# Propeller_board_rev_1_5.net
KiCad netlist of a schematic drawn in EAGLE
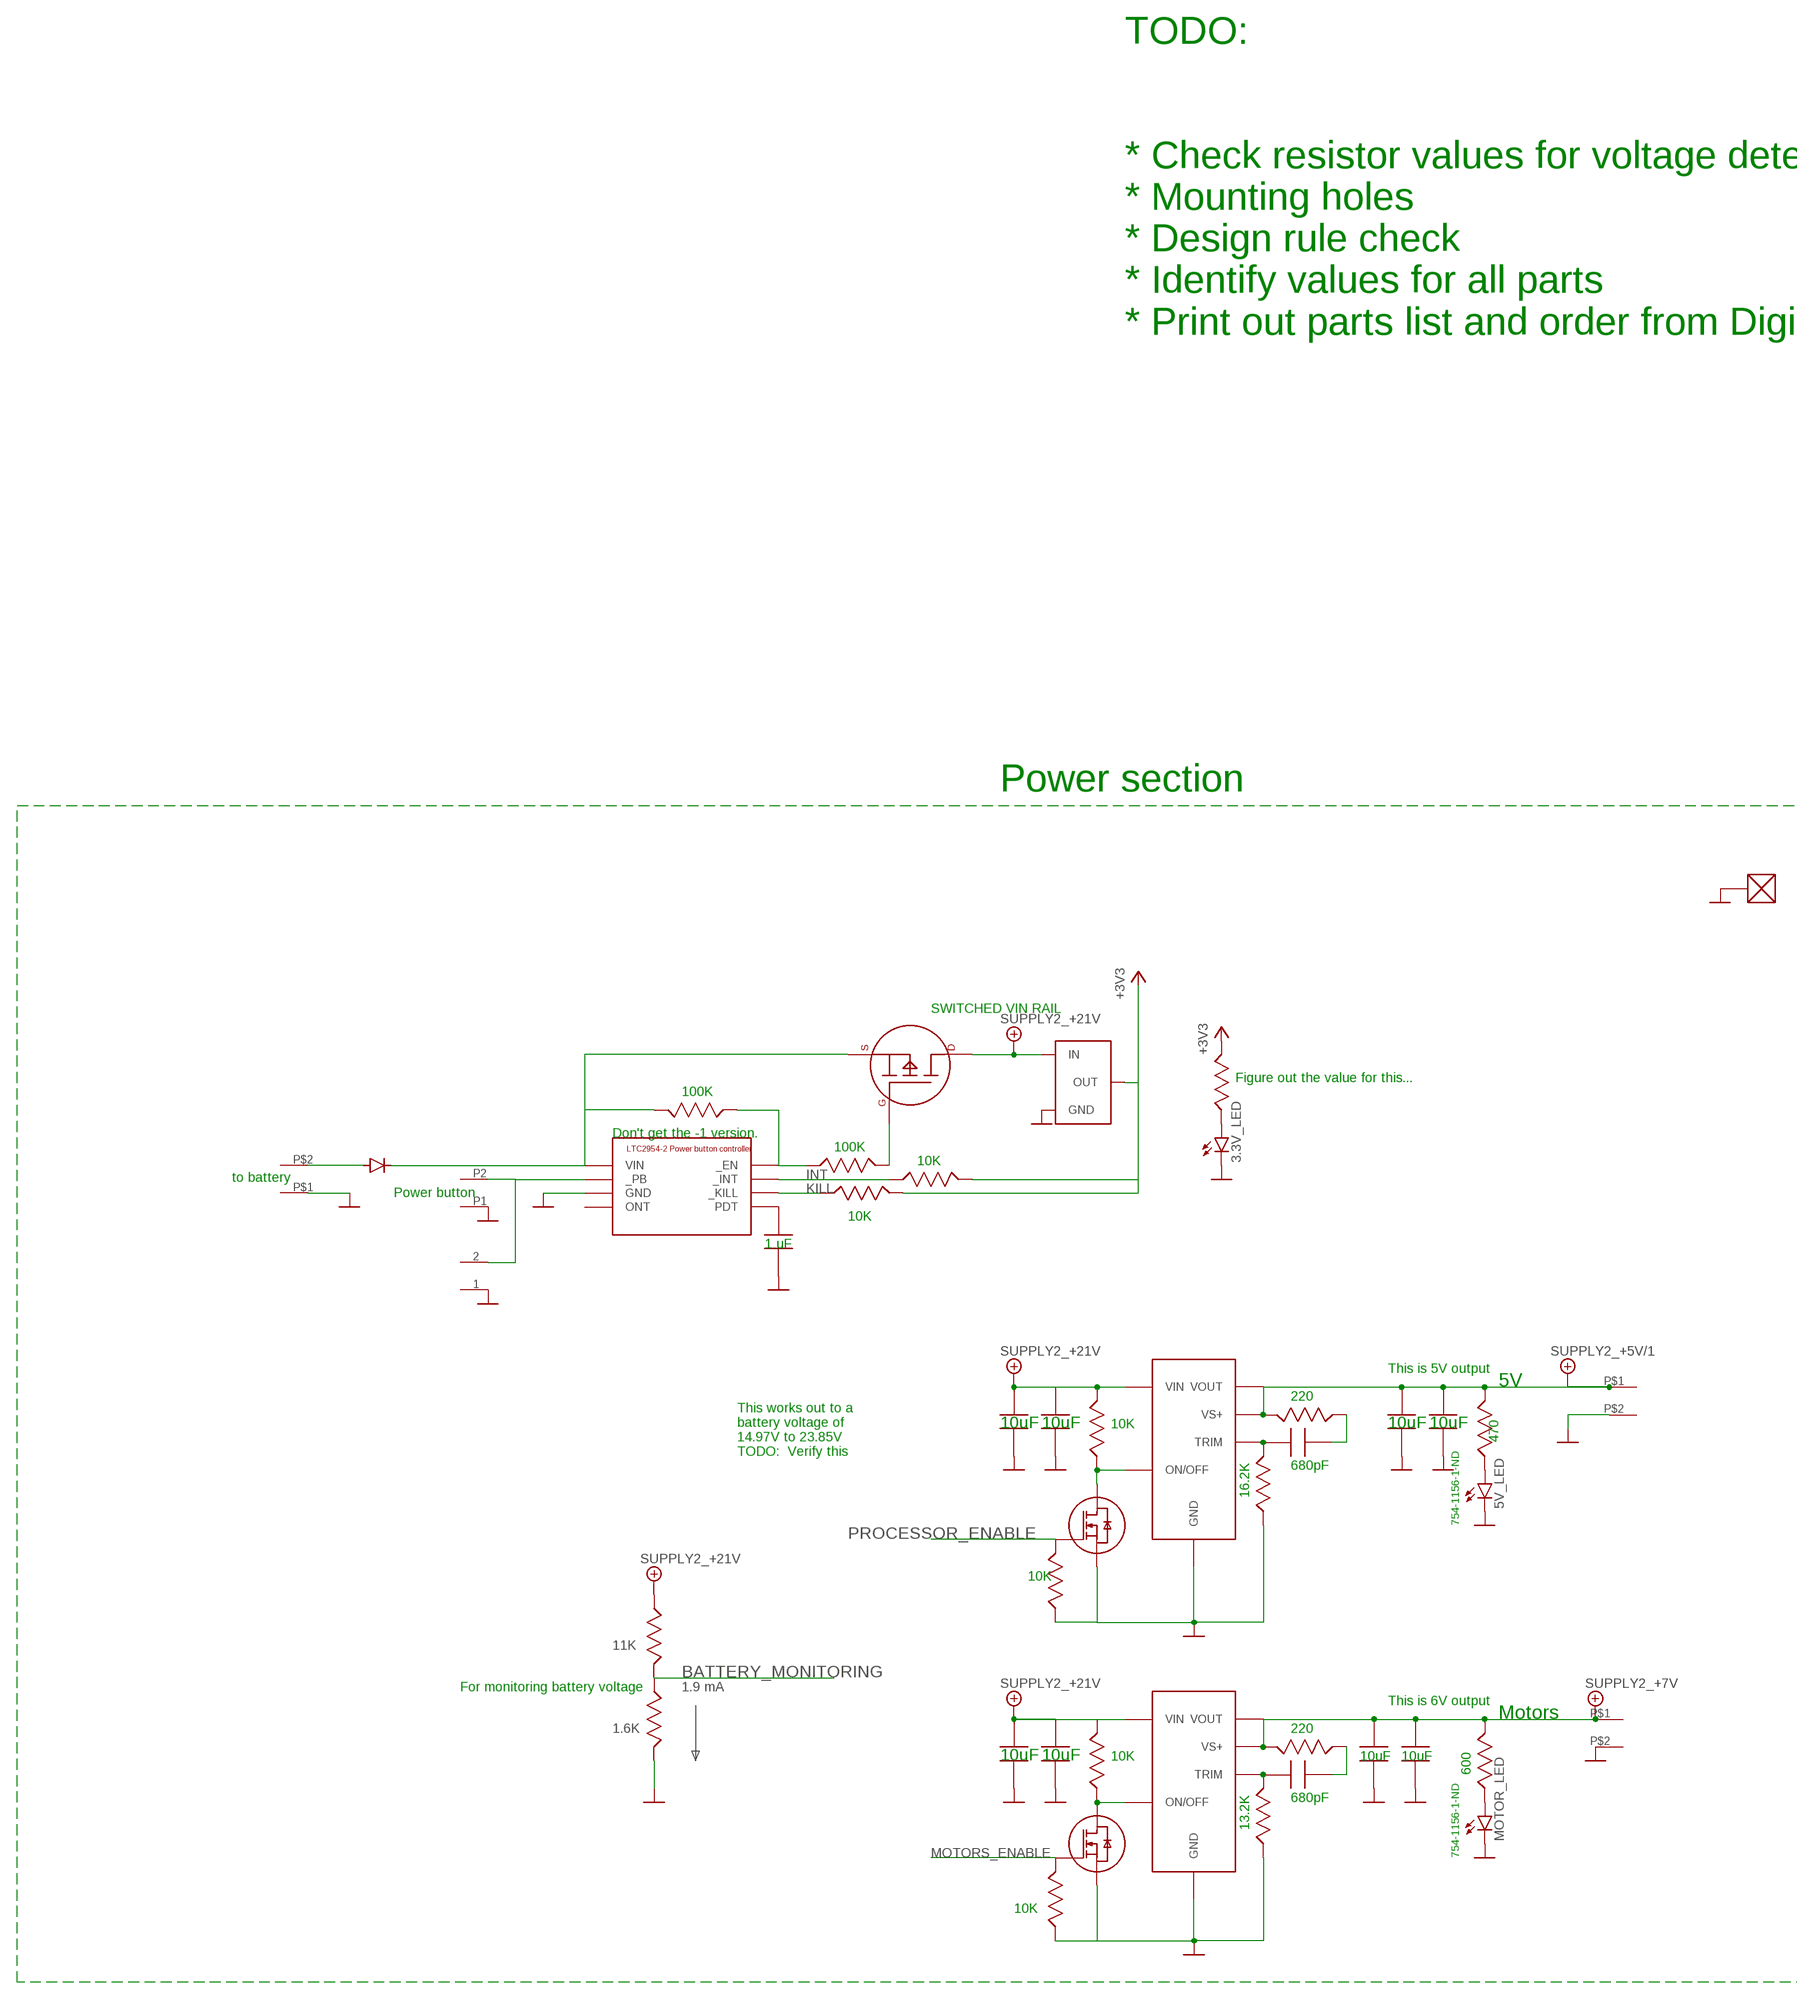
[diagram p0: schematic, sheet 1, part 1 of 2]
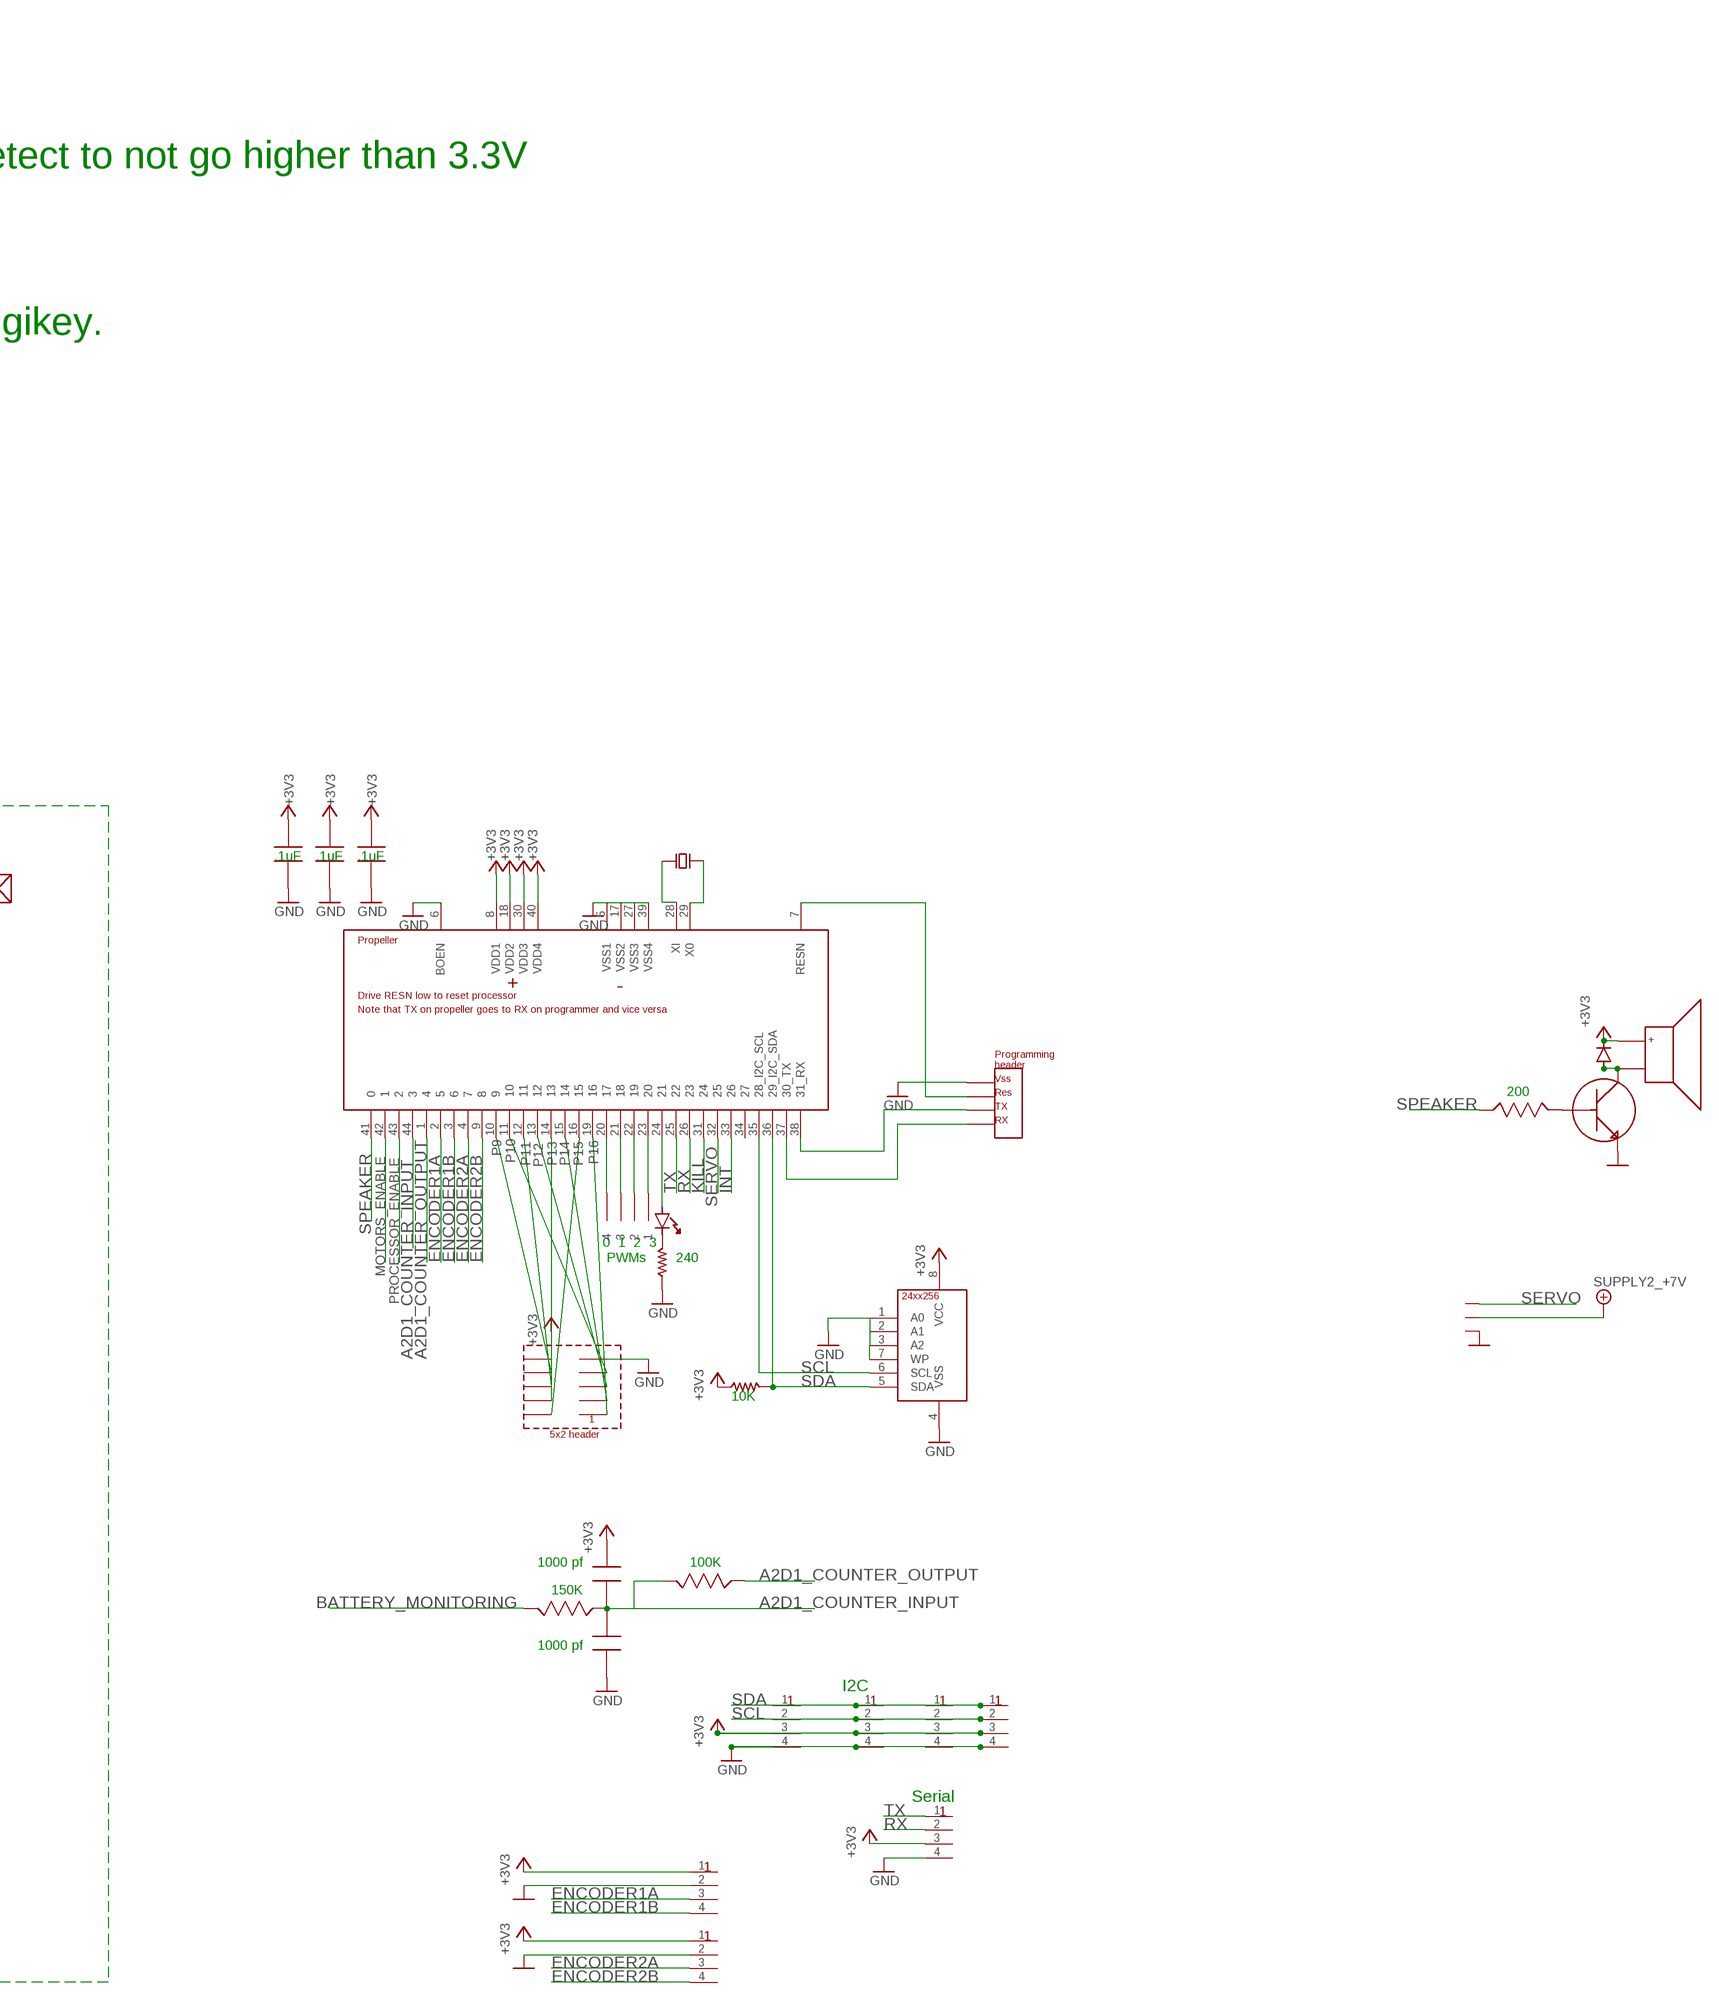
[diagram p1: schematic, sheet 1, part 2 of 2]

(export (version "E")
  (design (tool "Eeschema 10.0.6"))
  (components
    (comp (ref "3.3V_LED")
      (value "LED_LEDSML1206")
      (footprint "eagle-import:LED_SML1206")
      (libsource (lib "eagle-import") (part "LED_LEDSML1206"))
    )
    (comp (ref "3V3_REGULATOR_FOR_PROPELLER")
      (value "VOLTAGE_REGULATOR_3_TERMINALXP_POWER_VR05_SERIES")
      (footprint "eagle-import:VR05_SERIES_VREG")
      (libsource (lib "eagle-import") (part "VOLTAGE_REGULATOR_3_TERMINALXP_POWER_VR05_SERIES"))
    )
    (comp (ref "5V_C_680PF")
      (value "680pf")
      (footprint "eagle-import:JACK_0805")
      (libsource (lib "eagle-import") (part "JACK_CAPACITOR0805"))
    )
    (comp (ref "5V_LED")
      (value "LED_LEDSML1206")
      (footprint "eagle-import:LED_SML1206")
      (libsource (lib "eagle-import") (part "LED_LEDSML1206"))
    )
    (comp (ref "5V_LED_R1")
      (value "470")
      (footprint "eagle-import:JACK_0805")
      (libsource (lib "eagle-import") (part "JACK_RESISTOR0805"))
    )
    (comp (ref "5V_LED_R2")
      (value "470")
      (footprint "eagle-import:JACK_0805")
      (libsource (lib "eagle-import") (part "JACK_RESISTOR0805"))
    )
    (comp (ref "5V_REGULATOR_PULLUP")
      (value "10K")
      (footprint "eagle-import:JACK_0805")
      (libsource (lib "eagle-import") (part "JACK_RESISTOR0805"))
    )
    (comp (ref "5V_R_220")
      (value "220")
      (footprint "eagle-import:JACK_0805")
      (libsource (lib "eagle-import") (part "JACK_RESISTOR0805"))
    )
    (comp (ref "BATTERY_VOLTAGE_DIVIDER_HIGH")
      (value "11K")
      (footprint "eagle-import:JACK_0805")
      (libsource (lib "eagle-import") (part "JACK_RESISTOR0805"))
    )
    (comp (ref "BATTERY_VOLTAGE_DIVIDER_LOW")
      (value "1.6K")
      (footprint "eagle-import:JACK_0805")
      (libsource (lib "eagle-import") (part "JACK_RESISTOR0805"))
    )
    (comp (ref "MOTOR_C_680PF")
      (value "680pf")
      (footprint "eagle-import:JACK_0805")
      (libsource (lib "eagle-import") (part "JACK_CAPACITOR0805"))
    )
    (comp (ref "MOTOR_ENABLE_MOSFET")
      (value "JACK_MOSFET_N_CHANNELBSS138LCT-ND")
      (footprint "eagle-import:JACK_SOT23")
      (libsource (lib "eagle-import") (part "JACK_MOSFET_N_CHANNELBSS138LCT-ND"))
    )
    (comp (ref "MOTOR_ENABLE_MOSFET1")
      (value "JACK_MOSFET_N_CHANNELBSS138LCT-ND")
      (footprint "eagle-import:JACK_SOT23")
      (libsource (lib "eagle-import") (part "JACK_MOSFET_N_CHANNELBSS138LCT-ND"))
    )
    (comp (ref "MOTOR_LED")
      (value "LED_LEDSML1206")
      (footprint "eagle-import:LED_SML1206")
      (libsource (lib "eagle-import") (part "LED_LEDSML1206"))
    )
    (comp (ref "MOTOR_LED_R")
      (value "600")
      (footprint "eagle-import:JACK_0805")
      (libsource (lib "eagle-import") (part "JACK_RESISTOR0805"))
    )
    (comp (ref "MOTOR_MOSFET_PULLDOWN")
      (value "10K")
      (footprint "eagle-import:JACK_0805")
      (libsource (lib "eagle-import") (part "JACK_RESISTOR0805"))
    )
    (comp (ref "MOTOR_PULLUP")
      (value "10K")
      (footprint "eagle-import:JACK_0805")
      (libsource (lib "eagle-import") (part "JACK_RESISTOR0805"))
    )
    (comp (ref "MOTOR_PULLUP2")
      (value "10K")
      (footprint "eagle-import:JACK_0805")
      (libsource (lib "eagle-import") (part "JACK_RESISTOR0805"))
    )
    (comp (ref "MOTOR_R_220")
      (value "220")
      (footprint "eagle-import:JACK_0805")
      (libsource (lib "eagle-import") (part "JACK_RESISTOR0805"))
    )
    (comp (ref "MOTOR_TRIM")
      (value "13.2K")
      (footprint "eagle-import:JACK_0805")
      (libsource (lib "eagle-import") (part "JACK_RESISTOR0805"))
    )
    (comp (ref "R1")
      (value "240")
      (footprint "eagle-import:805_SMD")
      (libsource (lib "eagle-import") (part "jack_custom_RESISTOR0805"))
    )
    (comp (ref "R25")
      (value "10k")
      (footprint "eagle-import:805_SMD")
      (libsource (lib "eagle-import") (part "jack_custom_RESISTOR0805"))
    )
    (comp (ref "RTRIM_5V")
      (value "16.2K")
      (footprint "eagle-import:JACK_0805")
      (libsource (lib "eagle-import") (part "JACK_RESISTOR0805"))
    )
    (comp (ref "U$1")
      (value "CONNECTOR_2_PINJST_PH_SERIES")
      (footprint "eagle-import:JST_2_PIN_PH_SERIES")
      (libsource (lib "eagle-import") (part "CONNECTOR_2_PINJST_PH_SERIES"))
    )
    (comp (ref "U$2")
      (value "JACK_SCREW_TERMINAL_2_CONDUCTORAMP-282837-2")
      (footprint "eagle-import:JACK_AMP-282837-2")
      (libsource (lib "eagle-import") (part "JACK_SCREW_TERMINAL_2_CONDUCTORAMP-282837-2"))
    )
    (comp (ref "U$3")
      (value "POWER_CONTROLLER_LTC2954-2TSOT-23-8")
      (footprint "eagle-import:TSOT-23-8")
      (libsource (lib "eagle-import") (part "POWER_CONTROLLER_LTC2954-2TSOT-23-8"))
    )
    (comp (ref "U$4")
      (value "JACK_DC_TO_DC_VARIABLE_555-1172-1-ND")
      (footprint "eagle-import:JACK_DC2DC_555-1172-1-ND")
      (libsource (lib "eagle-import") (part "JACK_DC_TO_DC_VARIABLE_555-1172-1-ND"))
    )
    (comp (ref "U$5")
      (value "1uf")
      (footprint "eagle-import:0805")
      (libsource (lib "eagle-import") (part "CAPACITOR0805"))
    )
    (comp (ref "U$6")
      (value "JACK_SCREW_TERMINAL_2_CONDUCTORAMP-282837-2")
      (footprint "eagle-import:JACK_AMP-282837-2")
      (libsource (lib "eagle-import") (part "JACK_SCREW_TERMINAL_2_CONDUCTORAMP-282837-2"))
    )
    (comp (ref "U$7")
      (value "100K")
      (footprint "eagle-import:0805")
      (libsource (lib "eagle-import") (part "RESISTOR0805"))
    )
    (comp (ref "U$9")
      (value "100K")
      (footprint "eagle-import:0805")
      (libsource (lib "eagle-import") (part "RESISTOR0805"))
    )
    (comp (ref "U$10")
      (value "10K")
      (footprint "eagle-import:0805")
      (libsource (lib "eagle-import") (part "RESISTOR0805"))
    )
    (comp (ref "U$11")
      (value "1000pF or 1nF")
      (footprint "eagle-import:0805")
      (libsource (lib "eagle-import") (part "CAPACITOR0805"))
    )
    (comp (ref "U$12")
      (value "MOSFET_P_CHANNELSI4431CDY")
      (footprint "eagle-import:SO8")
      (libsource (lib "eagle-import") (part "MOSFET_P_CHANNELSI4431CDY"))
    )
    (comp (ref "U$13")
      (value "JACK_SCREW_TERMINAL_2_CONDUCTORAMP-282837-2")
      (footprint "eagle-import:JACK_AMP-282837-2")
      (libsource (lib "eagle-import") (part "JACK_SCREW_TERMINAL_2_CONDUCTORAMP-282837-2"))
    )
    (comp (ref "U$14")
      (value ".1uf")
      (footprint "eagle-import:0805")
      (libsource (lib "eagle-import") (part "CAPACITOR0805"))
    )
    (comp (ref "U$15")
      (value "CRYSTAL8X4.5_PACKAGE")
      (footprint "eagle-import:CRYSTAL_NX8045GB-5MHZ-STD-CSF-3")
      (libsource (lib "eagle-import") (part "CRYSTAL8X4.5_PACKAGE"))
    )
    (comp (ref "U$16")
      (value ".1uf")
      (footprint "eagle-import:0805")
      (libsource (lib "eagle-import") (part "CAPACITOR0805"))
    )
    (comp (ref "U$17")
      (value "JACK_DC_TO_DC_VARIABLE_555-1172-1-ND")
      (footprint "eagle-import:JACK_DC2DC_555-1172-1-ND")
      (libsource (lib "eagle-import") (part "JACK_DC_TO_DC_VARIABLE_555-1172-1-ND"))
    )
    (comp (ref "U$18")
      (value ".1uf")
      (footprint "eagle-import:0805")
      (libsource (lib "eagle-import") (part "CAPACITOR0805"))
    )
    (comp (ref "U$19")
      (value "TEST_POINT")
      (footprint "eagle-import:KEYSTONE_ELECTRONICS_5118_TEST_POINT")
      (libsource (lib "eagle-import") (part "TEST_POINT"))
    )
    (comp (ref "U$20")
      (value "LED0805")
      (footprint "eagle-import:0805")
      (libsource (lib "eagle-import") (part "LED0805"))
    )
    (comp (ref "U$21")
      (value "HEADER_4_PIN_.1\"")
      (footprint "eagle-import:FOUR_.1__HOLES")
      (libsource (lib "eagle-import") (part "HEADER_4_PIN_.1{dblquote}"))
    )
    (comp (ref "U$22")
      (value "HEADER_5X2")
      (footprint "eagle-import:HEADER_5X2_.1__SPACING")
      (libsource (lib "eagle-import") (part "HEADER_5X2"))
    )
    (comp (ref "U$23")
      (value "CONNECTOR_4_PINJST_PH_SERIES")
      (footprint "eagle-import:JST_4_PIN_PH_SERIES")
      (libsource (lib "eagle-import") (part "CONNECTOR_4_PINJST_PH_SERIES"))
    )
    (comp (ref "U$24")
      (value "CONNECTOR_4_PINJST_PH_SERIES")
      (footprint "eagle-import:JST_4_PIN_PH_SERIES")
      (libsource (lib "eagle-import") (part "CONNECTOR_4_PINJST_PH_SERIES"))
    )
    (comp (ref "U$25")
      (value "CONNECTOR_4_PINJST_PH_SERIES")
      (footprint "eagle-import:JST_4_PIN_PH_SERIES")
      (libsource (lib "eagle-import") (part "CONNECTOR_4_PINJST_PH_SERIES"))
    )
    (comp (ref "U$26")
      (value "CONNECTOR_2_PINJST_.1\"")
      (footprint "eagle-import:JST_2_PIN_.1_")
      (libsource (lib "eagle-import") (part "CONNECTOR_2_PINJST_.1{dblquote}"))
    )
    (comp (ref "U$27")
      (value "10K")
      (footprint "eagle-import:0805")
      (libsource (lib "eagle-import") (part "RESISTOR0805"))
    )
    (comp (ref "U$28")
      (value "10uF")
      (footprint "eagle-import:1210")
      (libsource (lib "eagle-import") (part "CAPACITOR"))
    )
    (comp (ref "U$29")
      (value "10uF")
      (footprint "eagle-import:1210")
      (libsource (lib "eagle-import") (part "CAPACITOR"))
    )
    (comp (ref "U$30")
      (value "10uf")
      (footprint "eagle-import:1210")
      (libsource (lib "eagle-import") (part "CAPACITOR"))
    )
    (comp (ref "U$31")
      (value "10uf")
      (footprint "eagle-import:1210")
      (libsource (lib "eagle-import") (part "CAPACITOR"))
    )
    (comp (ref "U$32")
      (value "10uf")
      (footprint "eagle-import:1210")
      (libsource (lib "eagle-import") (part "CAPACITOR"))
    )
    (comp (ref "U$33")
      (value "10uf")
      (footprint "eagle-import:1210")
      (libsource (lib "eagle-import") (part "CAPACITOR"))
    )
    (comp (ref "U$34")
      (value "SPEAKERGT-0950RP3")
      (footprint "eagle-import:AUDIO_TRANSDUCER_GT-0950RP3")
      (libsource (lib "eagle-import") (part "SPEAKERGT-0950RP3"))
    )
    (comp (ref "U$35")
      (value "DIODESOD523F")
      (footprint "eagle-import:SOD523F")
      (libsource (lib "eagle-import") (part "DIODESOD523F"))
    )
    (comp (ref "U$36")
      (value "TRANSISTOR_NPNMMBT3904")
      (footprint "eagle-import:SOT23")
      (libsource (lib "eagle-import") (part "TRANSISTOR_NPNMMBT3904"))
    )
    (comp (ref "U$37")
      (value "200")
      (footprint "eagle-import:0805")
      (libsource (lib "eagle-import") (part "RESISTOR0805"))
    )
    (comp (ref "U$38")
      (value "CONNECTOR_3_PIN.1\"SPACING")
      (footprint "eagle-import:THREE_.1__HOLES")
      (libsource (lib "eagle-import") (part "CONNECTOR_3_PIN.1{dblquote}SPACING"))
    )
    (comp (ref "U$39")
      (value "DIODEPOWER_DI15")
      (footprint "eagle-import:POWER_DI15")
      (libsource (lib "eagle-import") (part "DIODEPOWER_DI15"))
    )
    (comp (ref "U$40")
      (value "10uf")
      (footprint "eagle-import:1210")
      (libsource (lib "eagle-import") (part "CAPACITOR"))
    )
    (comp (ref "U$41")
      (value "10uf")
      (footprint "eagle-import:1210")
      (libsource (lib "eagle-import") (part "CAPACITOR"))
    )
    (comp (ref "U$42")
      (value "1000pf or 1 nF")
      (footprint "eagle-import:0805")
      (libsource (lib "eagle-import") (part "CAPACITOR0805"))
    )
    (comp (ref "U$43")
      (value "150K")
      (footprint "eagle-import:0805")
      (libsource (lib "eagle-import") (part "RESISTOR0805"))
    )
    (comp (ref "U$44")
      (value "100K")
      (footprint "eagle-import:0805")
      (libsource (lib "eagle-import") (part "RESISTOR0805"))
    )
    (comp (ref "U$45")
      (value "CONNECTOR_4_PINJST_PH_SERIES")
      (footprint "eagle-import:JST_4_PIN_PH_SERIES")
      (libsource (lib "eagle-import") (part "CONNECTOR_4_PINJST_PH_SERIES"))
    )
    (comp (ref "U$46")
      (value "CONNECTOR_4_PINJST_PH_SERIES")
      (footprint "eagle-import:JST_4_PIN_PH_SERIES")
      (libsource (lib "eagle-import") (part "CONNECTOR_4_PINJST_PH_SERIES"))
    )
    (comp (ref "U$47")
      (value "CONNECTOR_4_PINJST_PH_SERIES")
      (footprint "eagle-import:JST_4_PIN_PH_SERIES")
      (libsource (lib "eagle-import") (part "CONNECTOR_4_PINJST_PH_SERIES"))
    )
    (comp (ref "U$48")
      (value "PROPELLER_PROGRAMMING_HEADERHOLES")
      (footprint "eagle-import:FOUR_.1_HOLES")
      (libsource (lib "eagle-import") (part "PROPELLER_PROGRAMMING_HEADERHOLES"))
    )
    (comp (ref "U$49")
      (value "CONNECTOR_4_PINJST_PH_SERIES")
      (footprint "eagle-import:JST_4_PIN_PH_SERIES")
      (libsource (lib "eagle-import") (part "CONNECTOR_4_PINJST_PH_SERIES"))
    )
    (comp (ref "U1")
      (value "PARALLAX_PROPELLER")
      (footprint "eagle-import:44LQFP")
      (libsource (lib "eagle-import") (part "PARALLAX_PROPELLER"))
    )
    (comp (ref "U2")
      (value "EEPROM_24XX256")
      (footprint "eagle-import:8_MSOP")
      (libsource (lib "eagle-import") (part "EEPROM_24XX256"))
    )
  )
  (nets
    (net (code "1") (name "+3V3") (class "Default")
      (node (ref "3V3_REGULATOR_FOR_PROPELLER") (pin "VOUT") (pinfunction "OUT_VOUT") (pintype "bidirectional"))
      (node (ref "5V_LED_R2") (pin "P$3") (pinfunction "P$3_P$3") (pintype "bidirectional"))
      (node (ref "R25") (pin "P$1") (pinfunction "P$1_P$1") (pintype "bidirectional"))
      (node (ref "U$10") (pin "C2") (pinfunction "P$3_C2") (pintype "bidirectional"))
      (node (ref "U$11") (pin "C2") (pinfunction "2-_C2") (pintype "bidirectional"))
      (node (ref "U$14") (pin "C2") (pinfunction "2-_C2") (pintype "bidirectional"))
      (node (ref "U$16") (pin "C2") (pinfunction "2-_C2") (pintype "bidirectional"))
      (node (ref "U$18") (pin "C2") (pinfunction "2-_C2") (pintype "bidirectional"))
      (node (ref "U$22") (pin "P10") (pinfunction "10_P10") (pintype "bidirectional"))
      (node (ref "U$23") (pin "3") (pinfunction "P$3_3") (pintype "bidirectional"))
      (node (ref "U$24") (pin "3") (pinfunction "P$3_3") (pintype "bidirectional"))
      (node (ref "U$25") (pin "3") (pinfunction "P$3_3") (pintype "bidirectional"))
      (node (ref "U$27") (pin "C2") (pinfunction "P$3_C2") (pintype "bidirectional"))
      (node (ref "U$34") (pin "+") (pinfunction "+_+") (pintype "bidirectional"))
      (node (ref "U$35") (pin "C") (pinfunction "C_C") (pintype "bidirectional"))
      (node (ref "U$45") (pin "3") (pinfunction "P$3_3") (pintype "bidirectional"))
      (node (ref "U$46") (pin "1") (pinfunction "P$1_1") (pintype "bidirectional"))
      (node (ref "U$47") (pin "3") (pinfunction "P$3_3") (pintype "bidirectional"))
      (node (ref "U$49") (pin "1") (pinfunction "P$1_1") (pintype "bidirectional"))
      (node (ref "U1") (pin "18") (pinfunction "VDD2_18") (pintype "bidirectional"))
      (node (ref "U1") (pin "30") (pinfunction "VDD3_30") (pintype "bidirectional"))
      (node (ref "U1") (pin "40") (pinfunction "VDD4_40") (pintype "bidirectional"))
      (node (ref "U1") (pin "8") (pinfunction "VDD1_8") (pintype "bidirectional"))
      (node (ref "U2") (pin "8") (pinfunction "VCC_8") (pintype "bidirectional"))
    )
    (net (code "2") (name "/A2D1_COUNTER_INPUT") (class "Default")
      (node (ref "U$11") (pin "A1") (pinfunction "1+_A1") (pintype "bidirectional"))
      (node (ref "U$42") (pin "C2") (pinfunction "2-_C2") (pintype "bidirectional"))
      (node (ref "U$43") (pin "A1") (pinfunction "P$2_A1") (pintype "bidirectional"))
      (node (ref "U$44") (pin "C2") (pinfunction "P$3_C2") (pintype "bidirectional"))
      (node (ref "U1") (pin "44") (pinfunction "3_44") (pintype "bidirectional"))
    )
    (net (code "3") (name "/A2D1_COUNTER_OUTPUT") (class "Default")
      (node (ref "U$44") (pin "A1") (pinfunction "P$2_A1") (pintype "bidirectional"))
      (node (ref "U1") (pin "1") (pinfunction "4_1") (pintype "bidirectional"))
    )
    (net (code "4") (name "/BATTERY_MONITORING") (class "Default")
      (node (ref "BATTERY_VOLTAGE_DIVIDER_HIGH") (pin "P$3") (pinfunction "P$3_P$3") (pintype "bidirectional"))
      (node (ref "BATTERY_VOLTAGE_DIVIDER_LOW") (pin "P$2") (pinfunction "P$2_P$2") (pintype "bidirectional"))
      (node (ref "U$43") (pin "C2") (pinfunction "P$3_C2") (pintype "bidirectional"))
    )
    (net (code "5") (name "/ENCODER1A") (class "Default")
      (node (ref "U$46") (pin "3") (pinfunction "P$3_3") (pintype "bidirectional"))
      (node (ref "U1") (pin "2") (pinfunction "5_2") (pintype "bidirectional"))
    )
    (net (code "6") (name "/ENCODER1B") (class "Default")
      (node (ref "U$46") (pin "4") (pinfunction "P$4_4") (pintype "bidirectional"))
      (node (ref "U1") (pin "3") (pinfunction "6_3") (pintype "bidirectional"))
    )
    (net (code "7") (name "/ENCODER2A") (class "Default")
      (node (ref "U$49") (pin "3") (pinfunction "P$3_3") (pintype "bidirectional"))
      (node (ref "U1") (pin "4") (pinfunction "7_4") (pintype "bidirectional"))
    )
    (net (code "8") (name "/ENCODER2B") (class "Default")
      (node (ref "U$49") (pin "4") (pinfunction "P$4_4") (pintype "bidirectional"))
      (node (ref "U1") (pin "9") (pinfunction "8_9") (pintype "bidirectional"))
    )
    (net (code "9") (name "/INT") (class "Default")
      (node (ref "U$10") (pin "A1") (pinfunction "P$2_A1") (pintype "bidirectional"))
      (node (ref "U$3") (pin "5") (pinfunction "_INT_5") (pintype "bidirectional"))
      (node (ref "U1") (pin "33") (pinfunction "26_33") (pintype "bidirectional"))
    )
    (net (code "10") (name "/KILL") (class "Default")
      (node (ref "U$27") (pin "A1") (pinfunction "P$2_A1") (pintype "bidirectional"))
      (node (ref "U$3") (pin "8") (pinfunction "_KILL_8") (pintype "bidirectional"))
      (node (ref "U1") (pin "31") (pinfunction "24_31") (pintype "bidirectional"))
    )
    (net (code "11") (name "/MOTORS_ENABLE") (class "Default")
      (node (ref "MOTOR_ENABLE_MOSFET") (pin "1") (pinfunction "G_1") (pintype "bidirectional"))
      (node (ref "MOTOR_MOSFET_PULLDOWN") (pin "P$3") (pinfunction "P$3_P$3") (pintype "bidirectional"))
      (node (ref "U1") (pin "42") (pinfunction "1_42") (pintype "bidirectional"))
    )
    (net (code "12") (name "/P9") (class "Default")
      (node (ref "U$22") (pin "P8") (pinfunction "8_P8") (pintype "bidirectional"))
      (node (ref "U1") (pin "10") (pinfunction "9_10") (pintype "bidirectional"))
    )
    (net (code "13") (name "/P10") (class "Default")
      (node (ref "U$22") (pin "P7") (pinfunction "7_P7") (pintype "bidirectional"))
      (node (ref "U1") (pin "11") (pinfunction "10_11") (pintype "bidirectional"))
    )
    (net (code "14") (name "/P11") (class "Default")
      (node (ref "U$22") (pin "P6") (pinfunction "6_P6") (pintype "bidirectional"))
      (node (ref "U1") (pin "12") (pinfunction "11_12") (pintype "bidirectional"))
    )
    (net (code "15") (name "/P12") (class "Default")
      (node (ref "U$22") (pin "P5") (pinfunction "5_P5") (pintype "bidirectional"))
      (node (ref "U1") (pin "13") (pinfunction "12_13") (pintype "bidirectional"))
    )
    (net (code "16") (name "/P13") (class "Default")
      (node (ref "U$22") (pin "P4") (pinfunction "4_P4") (pintype "bidirectional"))
      (node (ref "U1") (pin "14") (pinfunction "13_14") (pintype "bidirectional"))
    )
    (net (code "17") (name "/P14") (class "Default")
      (node (ref "U$22") (pin "P3") (pinfunction "3_P3") (pintype "bidirectional"))
      (node (ref "U1") (pin "15") (pinfunction "14_15") (pintype "bidirectional"))
    )
    (net (code "18") (name "/P15") (class "Default")
      (node (ref "U$22") (pin "P2") (pinfunction "2_P2") (pintype "bidirectional"))
      (node (ref "U1") (pin "16") (pinfunction "15_16") (pintype "bidirectional"))
    )
    (net (code "19") (name "/P16") (class "Default")
      (node (ref "U$22") (pin "P1") (pinfunction "1_P1") (pintype "bidirectional"))
      (node (ref "U1") (pin "19") (pinfunction "16_19") (pintype "bidirectional"))
    )
    (net (code "20") (name "/PROCESSOR_ENABLE") (class "Default")
      (node (ref "MOTOR_ENABLE_MOSFET1") (pin "1") (pinfunction "G_1") (pintype "bidirectional"))
      (node (ref "MOTOR_PULLUP2") (pin "P$3") (pinfunction "P$3_P$3") (pintype "bidirectional"))
      (node (ref "U1") (pin "43") (pinfunction "2_43") (pintype "bidirectional"))
    )
    (net (code "21") (name "/RX") (class "Default")
      (node (ref "U$47") (pin "2") (pinfunction "P$2_2") (pintype "bidirectional"))
      (node (ref "U1") (pin "26") (pinfunction "23_26") (pintype "bidirectional"))
    )
    (net (code "22") (name "/SCL") (class "Default")
      (node (ref "U$23") (pin "2") (pinfunction "P$2_2") (pintype "bidirectional"))
      (node (ref "U$24") (pin "2") (pinfunction "P$2_2") (pintype "bidirectional"))
      (node (ref "U$25") (pin "2") (pinfunction "P$2_2") (pintype "bidirectional"))
      (node (ref "U$45") (pin "2") (pinfunction "P$2_2") (pintype "bidirectional"))
      (node (ref "U1") (pin "35") (pinfunction "28_I2C_SCL_35") (pintype "bidirectional"))
      (node (ref "U2") (pin "6") (pinfunction "SCL_6") (pintype "bidirectional"))
    )
    (net (code "23") (name "/SDA") (class "Default")
      (node (ref "R25") (pin "P$2") (pinfunction "P$2_P$2") (pintype "bidirectional"))
      (node (ref "U$23") (pin "1") (pinfunction "P$1_1") (pintype "bidirectional"))
      (node (ref "U$24") (pin "1") (pinfunction "P$1_1") (pintype "bidirectional"))
      (node (ref "U$25") (pin "1") (pinfunction "P$1_1") (pintype "bidirectional"))
      (node (ref "U$45") (pin "1") (pinfunction "P$1_1") (pintype "bidirectional"))
      (node (ref "U1") (pin "36") (pinfunction "29_I2C_SDA_36") (pintype "bidirectional"))
      (node (ref "U2") (pin "5") (pinfunction "SDA_5") (pintype "bidirectional"))
    )
    (net (code "24") (name "/SERVO") (class "Default")
      (node (ref "U$38") (pin "3") (pinfunction "3_3") (pintype "bidirectional"))
      (node (ref "U1") (pin "32") (pinfunction "25_32") (pintype "bidirectional"))
    )
    (net (code "25") (name "/SPEAKER") (class "Default")
      (node (ref "U$37") (pin "A1") (pinfunction "P$2_A1") (pintype "bidirectional"))
      (node (ref "U1") (pin "41") (pinfunction "0_41") (pintype "bidirectional"))
    )
    (net (code "26") (name "/TX") (class "Default")
      (node (ref "U$47") (pin "1") (pinfunction "P$1_1") (pintype "bidirectional"))
      (node (ref "U1") (pin "25") (pinfunction "22_25") (pintype "bidirectional"))
    )
    (net (code "27") (name "GND") (class "Default")
      (node (ref "3.3V_LED") (pin "C") (pinfunction "C_C") (pintype "passive"))
      (node (ref "3V3_REGULATOR_FOR_PROPELLER") (pin "GND") (pinfunction "GND_GND") (pintype "bidirectional"))
      (node (ref "5V_LED") (pin "C") (pinfunction "C_C") (pintype "passive"))
      (node (ref "BATTERY_VOLTAGE_DIVIDER_LOW") (pin "P$3") (pinfunction "P$3_P$3") (pintype "bidirectional"))
      (node (ref "MOTOR_ENABLE_MOSFET") (pin "2") (pinfunction "S_2") (pintype "bidirectional"))
      (node (ref "MOTOR_ENABLE_MOSFET1") (pin "2") (pinfunction "S_2") (pintype "bidirectional"))
      (node (ref "MOTOR_LED") (pin "C") (pinfunction "C_C") (pintype "passive"))
      (node (ref "MOTOR_MOSFET_PULLDOWN") (pin "P$2") (pinfunction "P$2_P$2") (pintype "bidirectional"))
      (node (ref "MOTOR_PULLUP2") (pin "P$2") (pinfunction "P$2_P$2") (pintype "bidirectional"))
      (node (ref "MOTOR_TRIM") (pin "P$2") (pinfunction "P$2_P$2") (pintype "bidirectional"))
      (node (ref "R1") (pin "P$1") (pinfunction "P$1_P$1") (pintype "bidirectional"))
      (node (ref "RTRIM_5V") (pin "P$2") (pinfunction "P$2_P$2") (pintype "bidirectional"))
      (node (ref "U$1") (pin "P1") (pinfunction "P$1_P1") (pintype "bidirectional"))
      (node (ref "U$13") (pin "P$2") (pinfunction "P$2_P$2") (pintype "bidirectional"))
      (node (ref "U$14") (pin "A1") (pinfunction "1+_A1") (pintype "bidirectional"))
      (node (ref "U$16") (pin "A1") (pinfunction "1+_A1") (pintype "bidirectional"))
      (node (ref "U$17") (pin "GND") (pinfunction "GND_GND") (pintype "bidirectional"))
      (node (ref "U$18") (pin "A1") (pinfunction "1+_A1") (pintype "bidirectional"))
      (node (ref "U$19") (pin "P1") (pinfunction "P$1_P1") (pintype "bidirectional"))
      (node (ref "U$2") (pin "P$2") (pinfunction "P$2_P$2") (pintype "bidirectional"))
      (node (ref "U$22") (pin "P9") (pinfunction "9_P9") (pintype "bidirectional"))
      (node (ref "U$23") (pin "4") (pinfunction "P$4_4") (pintype "bidirectional"))
      (node (ref "U$24") (pin "4") (pinfunction "P$4_4") (pintype "bidirectional"))
      (node (ref "U$25") (pin "4") (pinfunction "P$4_4") (pintype "bidirectional"))
      (node (ref "U$26") (pin "1") (pinfunction "P$1_1") (pintype "bidirectional"))
      (node (ref "U$28") (pin "1") (pinfunction "1+_1") (pintype "bidirectional"))
      (node (ref "U$29") (pin "1") (pinfunction "1+_1") (pintype "bidirectional"))
      (node (ref "U$3") (pin "4") (pinfunction "GND_4") (pintype "bidirectional"))
      (node (ref "U$30") (pin "1") (pinfunction "1+_1") (pintype "bidirectional"))
      (node (ref "U$31") (pin "1") (pinfunction "1+_1") (pintype "bidirectional"))
      (node (ref "U$32") (pin "1") (pinfunction "1+_1") (pintype "bidirectional"))
      (node (ref "U$33") (pin "1") (pinfunction "1+_1") (pintype "bidirectional"))
      (node (ref "U$36") (pin "2") (pinfunction "E_2") (pintype "bidirectional"))
      (node (ref "U$38") (pin "1") (pinfunction "1_1") (pintype "bidirectional"))
      (node (ref "U$4") (pin "GND") (pinfunction "GND_GND") (pintype "bidirectional"))
      (node (ref "U$40") (pin "1") (pinfunction "1+_1") (pintype "bidirectional"))
      (node (ref "U$41") (pin "1") (pinfunction "1+_1") (pintype "bidirectional"))
      (node (ref "U$42") (pin "A1") (pinfunction "1+_A1") (pintype "bidirectional"))
      (node (ref "U$45") (pin "4") (pinfunction "P$4_4") (pintype "bidirectional"))
      (node (ref "U$46") (pin "2") (pinfunction "P$2_2") (pintype "bidirectional"))
      (node (ref "U$47") (pin "4") (pinfunction "P$4_4") (pintype "bidirectional"))
      (node (ref "U$48") (pin "1") (pinfunction "VSS_1") (pintype "bidirectional"))
      (node (ref "U$49") (pin "2") (pinfunction "P$2_2") (pintype "bidirectional"))
      (node (ref "U$5") (pin "A1") (pinfunction "1+_A1") (pintype "bidirectional"))
      (node (ref "U$6") (pin "P$1") (pinfunction "P$1_P$1") (pintype "bidirectional"))
      (node (ref "U1") (pin "17") (pinfunction "VSS2_17") (pintype "bidirectional"))
      (node (ref "U1") (pin "27") (pinfunction "VSS3_27") (pintype "bidirectional"))
      (node (ref "U1") (pin "39") (pinfunction "VSS4_39") (pintype "bidirectional"))
      (node (ref "U1") (pin "5") (pinfunction "VSS1_5") (pintype "bidirectional"))
      (node (ref "U1") (pin "6") (pinfunction "BOEN_6") (pintype "bidirectional"))
      (node (ref "U2") (pin "1") (pinfunction "A0_1") (pintype "bidirectional"))
      (node (ref "U2") (pin "2") (pinfunction "A1_2") (pintype "bidirectional"))
      (node (ref "U2") (pin "3") (pinfunction "A2_3") (pintype "bidirectional"))
      (node (ref "U2") (pin "4") (pinfunction "VSS_4") (pintype "bidirectional"))
      (node (ref "U2") (pin "7") (pinfunction "WP_7") (pintype "bidirectional"))
    )
    (net (code "28") (name "Net-(3.3V_LED-PadA)") (class "Default")
      (node (ref "3.3V_LED") (pin "A") (pinfunction "A_A") (pintype "passive"))
      (node (ref "5V_LED_R2") (pin "P$2") (pinfunction "P$2_P$2") (pintype "bidirectional"))
    )
    (net (code "29") (name "Net-(5V_C_680PF-1)") (class "Default")
      (node (ref "5V_C_680PF") (pin "P$2") (pinfunction "1_P$2") (pintype "bidirectional"))
      (node (ref "5V_R_220") (pin "P$2") (pinfunction "P$2_P$2") (pintype "bidirectional"))
    )
    (net (code "30") (name "Net-(5V_C_680PF-2)") (class "Default")
      (node (ref "5V_C_680PF") (pin "P$3") (pinfunction "2_P$3") (pintype "bidirectional"))
      (node (ref "RTRIM_5V") (pin "P$3") (pinfunction "P$3_P$3") (pintype "bidirectional"))
      (node (ref "U$4") (pin "TRIM") (pinfunction "TRIM_TRIM") (pintype "bidirectional"))
    )
    (net (code "31") (name "Net-(5V_LED-PadA)") (class "Default")
      (node (ref "5V_LED") (pin "A") (pinfunction "A_A") (pintype "passive"))
      (node (ref "5V_LED_R1") (pin "P$2") (pinfunction "P$2_P$2") (pintype "bidirectional"))
    )
    (net (code "32") (name "Net-(MOTOR_C_680PF-1)") (class "Default")
      (node (ref "MOTOR_C_680PF") (pin "P$2") (pinfunction "1_P$2") (pintype "bidirectional"))
      (node (ref "MOTOR_R_220") (pin "P$2") (pinfunction "P$2_P$2") (pintype "bidirectional"))
    )
    (net (code "33") (name "Net-(MOTOR_C_680PF-2)") (class "Default")
      (node (ref "MOTOR_C_680PF") (pin "P$3") (pinfunction "2_P$3") (pintype "bidirectional"))
      (node (ref "MOTOR_TRIM") (pin "P$3") (pinfunction "P$3_P$3") (pintype "bidirectional"))
      (node (ref "U$17") (pin "TRIM") (pinfunction "TRIM_TRIM") (pintype "bidirectional"))
    )
    (net (code "34") (name "Net-(MOTOR_ENABLE_MOSFET-D)") (class "Default")
      (node (ref "MOTOR_ENABLE_MOSFET") (pin "3") (pinfunction "D_3") (pintype "bidirectional"))
      (node (ref "MOTOR_PULLUP") (pin "P$2") (pinfunction "P$2_P$2") (pintype "bidirectional"))
      (node (ref "U$17") (pin "ON/OFF") (pinfunction "ON/OFF_ON/OFF") (pintype "bidirectional"))
    )
    (net (code "35") (name "Net-(MOTOR_ENABLE_MOSFET1-D)") (class "Default")
      (node (ref "5V_REGULATOR_PULLUP") (pin "P$2") (pinfunction "P$2_P$2") (pintype "bidirectional"))
      (node (ref "MOTOR_ENABLE_MOSFET1") (pin "3") (pinfunction "D_3") (pintype "bidirectional"))
      (node (ref "U$4") (pin "ON/OFF") (pinfunction "ON/OFF_ON/OFF") (pintype "bidirectional"))
    )
    (net (code "36") (name "Net-(MOTOR_LED-PadA)") (class "Default")
      (node (ref "MOTOR_LED") (pin "A") (pinfunction "A_A") (pintype "passive"))
      (node (ref "MOTOR_LED_R") (pin "P$2") (pinfunction "P$2_P$2") (pintype "bidirectional"))
    )
    (net (code "37") (name "Net-(U$1-P$2)") (class "Default")
      (node (ref "U$1") (pin "P2") (pinfunction "P$2_P2") (pintype "bidirectional"))
      (node (ref "U$26") (pin "2") (pinfunction "P$2_2") (pintype "bidirectional"))
      (node (ref "U$3") (pin "2") (pinfunction "_PB_2") (pintype "bidirectional"))
    )
    (net (code "38") (name "Net-(U$3-PDT)") (class "Default")
      (node (ref "U$3") (pin "7") (pinfunction "PDT_7") (pintype "bidirectional"))
      (node (ref "U$5") (pin "C2") (pinfunction "2-_C2") (pintype "bidirectional"))
    )
    (net (code "39") (name "Net-(U$3-VIN)") (class "Default")
      (node (ref "U$12") (pin "1") (pinfunction "S_1") (pintype "bidirectional"))
      (node (ref "U$12") (pin "2") (pinfunction "S_2") (pintype "bidirectional"))
      (node (ref "U$12") (pin "3") (pinfunction "S_3") (pintype "bidirectional"))
      (node (ref "U$3") (pin "1") (pinfunction "VIN_1") (pintype "bidirectional"))
      (node (ref "U$39") (pin "3") (pinfunction "C_3") (pintype "bidirectional"))
      (node (ref "U$7") (pin "C2") (pinfunction "P$3_C2") (pintype "bidirectional"))
    )
    (net (code "40") (name "Net-(U$3-_EN)") (class "Default")
      (node (ref "U$3") (pin "6") (pinfunction "_EN_6") (pintype "bidirectional"))
      (node (ref "U$7") (pin "A1") (pinfunction "P$2_A1") (pintype "bidirectional"))
      (node (ref "U$9") (pin "A1") (pinfunction "P$2_A1") (pintype "bidirectional"))
    )
    (net (code "41") (name "Net-(U$12-G)") (class "Default")
      (node (ref "U$12") (pin "4") (pinfunction "G_4") (pintype "bidirectional"))
      (node (ref "U$9") (pin "C2") (pinfunction "P$3_C2") (pintype "bidirectional"))
    )
    (net (code "42") (name "Net-(U$15-P$3)") (class "Default")
      (node (ref "U$15") (pin "1") (pinfunction "P$3_1") (pintype "bidirectional"))
      (node (ref "U1") (pin "28") (pinfunction "XI_28") (pintype "bidirectional"))
    )
    (net (code "43") (name "Net-(U$15-P$4)") (class "Default")
      (node (ref "U$15") (pin "2") (pinfunction "P$4_2") (pintype "bidirectional"))
      (node (ref "U1") (pin "29") (pinfunction "X0_29") (pintype "bidirectional"))
    )
    (net (code "44") (name "Net-(U$20-A)") (class "Default")
      (node (ref "U$20") (pin "A1") (pinfunction "A_A1") (pintype "bidirectional"))
      (node (ref "U1") (pin "24") (pinfunction "21_24") (pintype "bidirectional"))
    )
    (net (code "45") (name "Net-(U$20-C)") (class "Default")
      (node (ref "R1") (pin "P$2") (pinfunction "P$2_P$2") (pintype "bidirectional"))
      (node (ref "U$20") (pin "C2") (pinfunction "C_C2") (pintype "bidirectional"))
    )
    (net (code "46") (name "Net-(U$36-B)") (class "Default")
      (node (ref "U$36") (pin "1") (pinfunction "B_1") (pintype "bidirectional"))
      (node (ref "U$37") (pin "C2") (pinfunction "P$3_C2") (pintype "bidirectional"))
    )
    (net (code "47") (name "Net-(U$36-C)") (class "Default")
      (node (ref "U$34") (pin "-") (pinfunction "-_-") (pintype "bidirectional"))
      (node (ref "U$35") (pin "A") (pinfunction "A_A") (pintype "bidirectional"))
      (node (ref "U$36") (pin "3") (pinfunction "C_3") (pintype "bidirectional"))
    )
    (net (code "48") (name "Net-(U$39-A-Pad1)") (class "Default")
      (node (ref "U$39") (pin "1") (pinfunction "A_1") (pintype "bidirectional"))
      (node (ref "U$39") (pin "2") (pinfunction "A_2") (pintype "bidirectional"))
      (node (ref "U$6") (pin "P$2") (pinfunction "P$2_P$2") (pintype "bidirectional"))
    )
    (net (code "49") (name "Net-(U$48-RES)") (class "Default")
      (node (ref "U$48") (pin "2") (pinfunction "RES_2") (pintype "bidirectional"))
      (node (ref "U1") (pin "7") (pinfunction "RESN_7") (pintype "bidirectional"))
    )
    (net (code "50") (name "Net-(U$48-RX)") (class "Default")
      (node (ref "U$48") (pin "4") (pinfunction "RX_4") (pintype "bidirectional"))
      (node (ref "U1") (pin "37") (pinfunction "30_TX_37") (pintype "bidirectional"))
    )
    (net (code "51") (name "Net-(U$48-TX)") (class "Default")
      (node (ref "U$48") (pin "3") (pinfunction "TX_3") (pintype "bidirectional"))
      (node (ref "U1") (pin "38") (pinfunction "31_RX_38") (pintype "bidirectional"))
    )
    (net (code "52") (name "Net-(U1-17)") (class "Default")
      (node (ref "U$21") (pin "4") (pinfunction "4_4") (pintype "bidirectional"))
      (node (ref "U1") (pin "20") (pinfunction "17_20") (pintype "bidirectional"))
    )
    (net (code "53") (name "Net-(U1-18)") (class "Default")
      (node (ref "U$21") (pin "3") (pinfunction "3_3") (pintype "bidirectional"))
      (node (ref "U1") (pin "21") (pinfunction "18_21") (pintype "bidirectional"))
    )
    (net (code "54") (name "Net-(U1-19)") (class "Default")
      (node (ref "U$21") (pin "2") (pinfunction "2_2") (pintype "bidirectional"))
      (node (ref "U1") (pin "22") (pinfunction "19_22") (pintype "bidirectional"))
    )
    (net (code "55") (name "Net-(U1-20)") (class "Default")
      (node (ref "U$21") (pin "1") (pinfunction "1_1") (pintype "bidirectional"))
      (node (ref "U1") (pin "23") (pinfunction "20_23") (pintype "bidirectional"))
    )
    (net (code "56") (name "SUPPLY2_+5V{slash}1") (class "Default")
      (node (ref "5V_LED_R1") (pin "P$3") (pinfunction "P$3_P$3") (pintype "bidirectional"))
      (node (ref "5V_R_220") (pin "P$3") (pinfunction "P$3_P$3") (pintype "bidirectional"))
      (node (ref "U$2") (pin "P$1") (pinfunction "P$1_P$1") (pintype "bidirectional"))
      (node (ref "U$30") (pin "2") (pinfunction "2-_2") (pintype "bidirectional"))
      (node (ref "U$33") (pin "2") (pinfunction "2-_2") (pintype "bidirectional"))
      (node (ref "U$4") (pin "VOUT") (pinfunction "VOUT_VOUT") (pintype "bidirectional"))
      (node (ref "U$4") (pin "VS+") (pinfunction "VS+_VS+") (pintype "bidirectional"))
    )
    (net (code "57") (name "SUPPLY2_+7V") (class "Default")
      (node (ref "MOTOR_LED_R") (pin "P$3") (pinfunction "P$3_P$3") (pintype "bidirectional"))
      (node (ref "MOTOR_R_220") (pin "P$3") (pinfunction "P$3_P$3") (pintype "bidirectional"))
      (node (ref "U$13") (pin "P$1") (pinfunction "P$1_P$1") (pintype "bidirectional"))
      (node (ref "U$17") (pin "VOUT") (pinfunction "VOUT_VOUT") (pintype "bidirectional"))
      (node (ref "U$17") (pin "VS+") (pinfunction "VS+_VS+") (pintype "bidirectional"))
      (node (ref "U$32") (pin "2") (pinfunction "2-_2") (pintype "bidirectional"))
      (node (ref "U$38") (pin "2") (pinfunction "2_2") (pintype "bidirectional"))
      (node (ref "U$40") (pin "2") (pinfunction "2-_2") (pintype "bidirectional"))
    )
    (net (code "58") (name "SUPPLY2_+21V") (class "Default")
      (node (ref "3V3_REGULATOR_FOR_PROPELLER") (pin "VIN") (pinfunction "IN_VIN") (pintype "bidirectional"))
      (node (ref "5V_REGULATOR_PULLUP") (pin "P$3") (pinfunction "P$3_P$3") (pintype "bidirectional"))
      (node (ref "BATTERY_VOLTAGE_DIVIDER_HIGH") (pin "P$2") (pinfunction "P$2_P$2") (pintype "bidirectional"))
      (node (ref "MOTOR_PULLUP") (pin "P$3") (pinfunction "P$3_P$3") (pintype "bidirectional"))
      (node (ref "U$12") (pin "5") (pinfunction "D_5") (pintype "bidirectional"))
      (node (ref "U$12") (pin "6") (pinfunction "D_6") (pintype "bidirectional"))
      (node (ref "U$12") (pin "7") (pinfunction "D_7") (pintype "bidirectional"))
      (node (ref "U$12") (pin "8") (pinfunction "D_8") (pintype "bidirectional"))
      (node (ref "U$17") (pin "VIN") (pinfunction "VIN_VIN") (pintype "bidirectional"))
      (node (ref "U$28") (pin "2") (pinfunction "2-_2") (pintype "bidirectional"))
      (node (ref "U$29") (pin "2") (pinfunction "2-_2") (pintype "bidirectional"))
      (node (ref "U$31") (pin "2") (pinfunction "2-_2") (pintype "bidirectional"))
      (node (ref "U$4") (pin "VIN") (pinfunction "VIN_VIN") (pintype "bidirectional"))
      (node (ref "U$41") (pin "2") (pinfunction "2-_2") (pintype "bidirectional"))
    )
    (net (code "59") (name "unconnected-(U$3-ONT-Pad3)") (class "Default")
      (node (ref "U$3") (pin "3") (pinfunction "ONT_3") (pintype "bidirectional"))
    )
    (net (code "60") (name "unconnected-(U1-27-Pad34)") (class "Default")
      (node (ref "U1") (pin "34") (pinfunction "27_34") (pintype "bidirectional"))
    )
  )
)
